# Gobang.net
KiCad netlist of a schematic drawn in Altium Designer
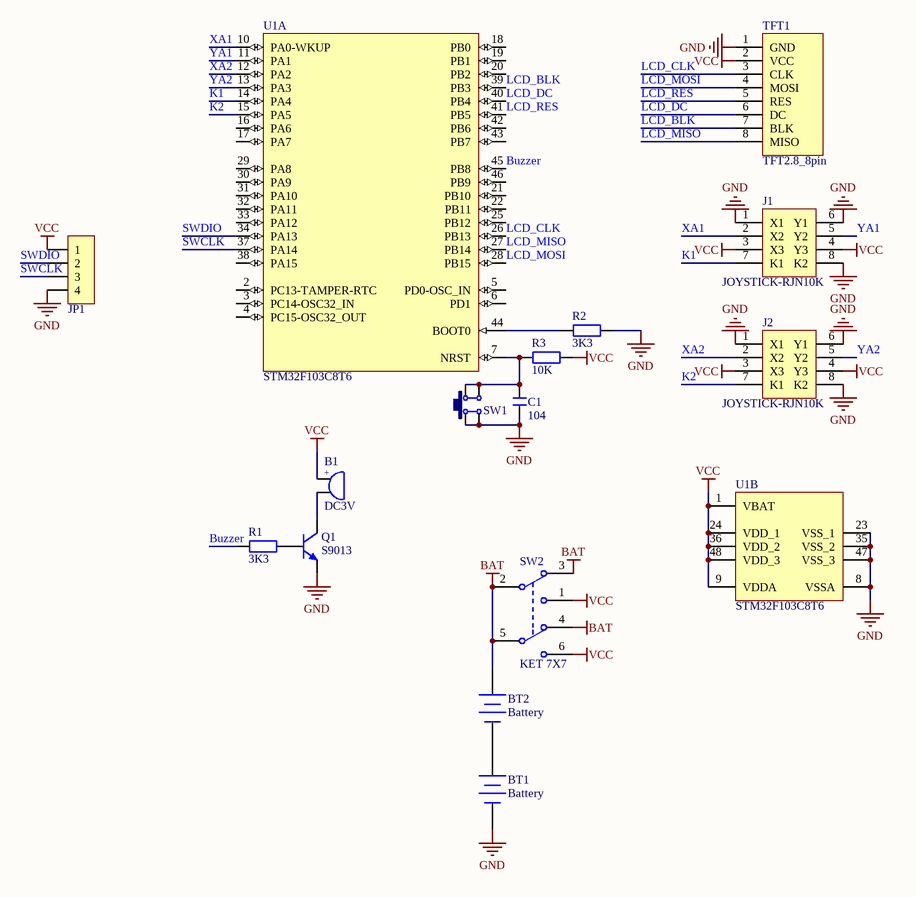
[diagram p0: Gobang.SchDoc]

(export (version "E")
  (design (tool "Eeschema 10.0.6"))
  (components
    (comp (ref "B1")
      (value "DC3V")
      (footprint "BEEP 6.5x12x8.5")
      (description "蜂鸣器")
      (fields (field (name "版权归属") "源创客"))
      (libsource (lib "未分类器件") (part "BEEP"))
    )
    (comp (ref "BT1")
      (value "Battery")
      (footprint "BATTERY AA x1")
      (description "Multicell Battery")
      (fields (field (name "PUBLISHER") "Altium Limited"))
      (libsource (lib "Miscellaneous Devices") (part "Battery"))
    )
    (comp (ref "BT2")
      (value "Battery")
      (footprint "BATTERY AA x1")
      (description "Multicell Battery")
      (fields (field (name "PUBLISHER") "Altium Limited"))
      (libsource (lib "Miscellaneous Devices") (part "Battery"))
    )
    (comp (ref "C1")
      (value "104")
      (footprint "C 0805")
      (description "无极性贴片电容")
      (fields (field (name "版权归属") "源创客"))
      (libsource (lib "电阻-电容-电感") (part "C"))
    )
    (comp (ref "J1")
      (value "JOYSTICK-RJN10K")
      (footprint "JOYSTICK-RJN10K")
      (libsource (lib "原理图库") (part "JOYSTICK-RJN10K"))
    )
    (comp (ref "J2")
      (value "JOYSTICK-RJN10K")
      (footprint "JOYSTICK-RJN10K")
      (libsource (lib "原理图库") (part "JOYSTICK-RJN10K"))
    )
    (comp (ref "JP1")
      (value "HDR-1X4")
      (footprint "HDR-1X4_H")
      (description "4P接插件")
      (fields (field (name "版权归属") "源创客"))
      (libsource (lib "接插件") (part "Header 4"))
    )
    (comp (ref "Q1")
      (value "S9013")
      (footprint "SOT23-3N")
      (description "低频放大-NPN型")
      (fields (field (name "版权归属") "源创客"))
      (libsource (lib "三极管") (part "9013-SMD"))
    )
    (comp (ref "R1")
      (value "3K3")
      (footprint "R 0603")
      (description "贴片电阻")
      (fields (field (name "版权归属") "源创客"))
      (libsource (lib "电阻-电容-电感") (part "R"))
    )
    (comp (ref "R2")
      (value "3K3")
      (footprint "R 0603")
      (description "贴片电阻")
      (fields (field (name "版权归属") "源创客"))
      (libsource (lib "电阻-电容-电感") (part "R"))
    )
    (comp (ref "R3")
      (value "10K")
      (footprint "R 0603")
      (description "贴片电阻")
      (fields (field (name "版权归属") "源创客"))
      (libsource (lib "电阻-电容-电感") (part "R"))
    )
    (comp (ref "SW1")
      (value "6x6x5")
      (footprint "TSW DIP-6*6*6")
      (description "直插6x6轻触开关")
      (fields (field (name "版权归属") "源创客"))
      (libsource (lib "按键-开关") (part "TSW DIP-6x6"))
    )
    (comp (ref "SW2")
      (value "KET 7X7")
      (footprint "KFT DIP-7X7")
      (description "7*7自锁开关")
      (fields (field (name "版权归属") "源创客"))
      (libsource (lib "按键-开关") (part "KET 7X7"))
    )
    (comp (ref "TFT1")
      (value "TFT2.8_8pin")
      (footprint "TFT2.8_8PIN")
      (description "240*320")
      (libsource (lib "显示器件") (part "TFT2.8_8pin"))
    )
    (comp (ref "U1")
      (value "STM32F103C8T6")
      (footprint "LQFP48_N")
      (libsource (lib "STMicroelectronics STM32 F1") (part "STM32F103C8T6"))
    )
  )
  (nets
    (net (code "1") (name "/Buzzer") (class "Default")
      (node (ref "R1") (pin "1") (pinfunction "1_1") (pintype "passive"))
      (node (ref "U1") (pin "45") (pinfunction "PB8_45") (pintype "bidirectional"))
    )
    (net (code "2") (name "/K1") (class "Default")
      (node (ref "J1") (pin "7") (pinfunction "K1_7") (pintype "passive"))
      (node (ref "U1") (pin "14") (pinfunction "PA4_14") (pintype "bidirectional"))
    )
    (net (code "3") (name "/K2") (class "Default")
      (node (ref "J2") (pin "7") (pinfunction "K1_7") (pintype "passive"))
      (node (ref "U1") (pin "15") (pinfunction "PA5_15") (pintype "bidirectional"))
    )
    (net (code "4") (name "/LCD_BLK") (class "Default")
      (node (ref "TFT1") (pin "7") (pinfunction "BLK_7") (pintype "passive"))
      (node (ref "U1") (pin "39") (pinfunction "PB3_39") (pintype "bidirectional"))
    )
    (net (code "5") (name "/LCD_CLK") (class "Default")
      (node (ref "TFT1") (pin "3") (pinfunction "CLK_3") (pintype "passive"))
      (node (ref "U1") (pin "26") (pinfunction "PB13_26") (pintype "bidirectional"))
    )
    (net (code "6") (name "/LCD_DC") (class "Default")
      (node (ref "TFT1") (pin "6") (pinfunction "DC_6") (pintype "passive"))
      (node (ref "U1") (pin "40") (pinfunction "PB4_40") (pintype "bidirectional"))
    )
    (net (code "7") (name "/LCD_MISO") (class "Default")
      (node (ref "TFT1") (pin "8") (pinfunction "MISO_8") (pintype "passive"))
      (node (ref "U1") (pin "27") (pinfunction "PB14_27") (pintype "bidirectional"))
    )
    (net (code "8") (name "/LCD_MOSI") (class "Default")
      (node (ref "TFT1") (pin "4") (pinfunction "MOSI_4") (pintype "passive"))
      (node (ref "U1") (pin "28") (pinfunction "PB15_28") (pintype "bidirectional"))
    )
    (net (code "9") (name "/LCD_RES") (class "Default")
      (node (ref "TFT1") (pin "5") (pinfunction "RES_5") (pintype "passive"))
      (node (ref "U1") (pin "41") (pinfunction "PB5_41") (pintype "bidirectional"))
    )
    (net (code "10") (name "/SWCLK") (class "Default")
      (node (ref "JP1") (pin "3") (pinfunction "3_3") (pintype "passive"))
      (node (ref "U1") (pin "37") (pinfunction "PA14_37") (pintype "bidirectional"))
    )
    (net (code "11") (name "/SWDIO") (class "Default")
      (node (ref "JP1") (pin "2") (pinfunction "2_2") (pintype "passive"))
      (node (ref "U1") (pin "34") (pinfunction "PA13_34") (pintype "bidirectional"))
    )
    (net (code "12") (name "/XA1") (class "Default")
      (node (ref "J1") (pin "2") (pinfunction "X2_2") (pintype "passive"))
      (node (ref "U1") (pin "10") (pinfunction "PA0-WKUP_10") (pintype "bidirectional"))
    )
    (net (code "13") (name "/XA2") (class "Default")
      (node (ref "J2") (pin "2") (pinfunction "X2_2") (pintype "passive"))
      (node (ref "U1") (pin "12") (pinfunction "PA2_12") (pintype "bidirectional"))
    )
    (net (code "14") (name "/YA1") (class "Default")
      (node (ref "J1") (pin "5") (pinfunction "Y2_5") (pintype "passive"))
      (node (ref "U1") (pin "11") (pinfunction "PA1_11") (pintype "bidirectional"))
    )
    (net (code "15") (name "/YA2") (class "Default")
      (node (ref "J2") (pin "5") (pinfunction "Y2_5") (pintype "passive"))
      (node (ref "U1") (pin "13") (pinfunction "PA3_13") (pintype "bidirectional"))
    )
    (net (code "16") (name "BAT") (class "Default")
      (node (ref "BT2") (pin "1") (pinfunction "+_1") (pintype "passive"))
      (node (ref "SW2") (pin "2") (pinfunction "COM2_2") (pintype "passive"))
      (node (ref "SW2") (pin "3") (pinfunction "NO1_3") (pintype "passive"))
      (node (ref "SW2") (pin "4") (pinfunction "NO2_4") (pintype "passive"))
      (node (ref "SW2") (pin "5") (pinfunction "COM2_5") (pintype "passive"))
    )
    (net (code "17") (name "GND") (class "Default")
      (node (ref "BT1") (pin "2") (pinfunction "-_2") (pintype "passive"))
      (node (ref "C1") (pin "1") (pinfunction "1_1") (pintype "passive"))
      (node (ref "J1") (pin "1") (pinfunction "X1_1") (pintype "passive"))
      (node (ref "J1") (pin "6") (pinfunction "Y1_6") (pintype "passive"))
      (node (ref "J1") (pin "8") (pinfunction "K2_8") (pintype "passive"))
      (node (ref "J2") (pin "1") (pinfunction "X1_1") (pintype "passive"))
      (node (ref "J2") (pin "6") (pinfunction "Y1_6") (pintype "passive"))
      (node (ref "J2") (pin "8") (pinfunction "K2_8") (pintype "passive"))
      (node (ref "JP1") (pin "4") (pinfunction "4_4") (pintype "passive"))
      (node (ref "Q1") (pin "2") (pinfunction "E_2") (pintype "passive"))
      (node (ref "R2") (pin "2") (pinfunction "2_2") (pintype "passive"))
      (node (ref "SW1") (pin "1") (pinfunction "1_1") (pintype "passive"))
      (node (ref "SW1") (pin "4") (pinfunction "4_4") (pintype "passive"))
      (node (ref "TFT1") (pin "1") (pinfunction "GND_1") (pintype "passive"))
      (node (ref "U1") (pin "23") (pinfunction "VSS_1_23") (pintype "power_in"))
      (node (ref "U1") (pin "35") (pinfunction "VSS_2_35") (pintype "power_in"))
      (node (ref "U1") (pin "47") (pinfunction "VSS_3_47") (pintype "power_in"))
      (node (ref "U1") (pin "8") (pinfunction "VSSA_8") (pintype "power_in"))
    )
    (net (code "18") (name "Net-(BT1-+)") (class "Default")
      (node (ref "BT1") (pin "1") (pinfunction "+_1") (pintype "passive"))
      (node (ref "BT2") (pin "2") (pinfunction "-_2") (pintype "passive"))
    )
    (net (code "19") (name "Net-(Q1-B)") (class "Default")
      (node (ref "Q1") (pin "1") (pinfunction "B_1") (pintype "passive"))
      (node (ref "R1") (pin "2") (pinfunction "2_2") (pintype "passive"))
    )
    (net (code "20") (name "Net-(Q1-C)") (class "Default")
      (node (ref "B1") (pin "K") (pinfunction "K_K") (pintype "passive"))
      (node (ref "Q1") (pin "3") (pinfunction "C_3") (pintype "passive"))
    )
    (net (code "21") (name "Net-(U1A-BOOT0)") (class "Default")
      (node (ref "R2") (pin "1") (pinfunction "1_1") (pintype "passive"))
      (node (ref "U1") (pin "44") (pinfunction "BOOT0_44") (pintype "input"))
    )
    (net (code "22") (name "Net-(U1A-NRST)") (class "Default")
      (node (ref "C1") (pin "2") (pinfunction "2_2") (pintype "passive"))
      (node (ref "R3") (pin "1") (pinfunction "1_1") (pintype "passive"))
      (node (ref "SW1") (pin "2") (pinfunction "2_2") (pintype "passive"))
      (node (ref "SW1") (pin "3") (pinfunction "3_3") (pintype "passive"))
      (node (ref "U1") (pin "7") (pinfunction "NRST_7") (pintype "bidirectional"))
    )
    (net (code "23") (name "VCC") (class "Default")
      (node (ref "B1") (pin "A") (pinfunction "A_A") (pintype "passive"))
      (node (ref "J1") (pin "3") (pinfunction "X3_3") (pintype "passive"))
      (node (ref "J1") (pin "4") (pinfunction "Y3_4") (pintype "passive"))
      (node (ref "J2") (pin "3") (pinfunction "X3_3") (pintype "passive"))
      (node (ref "J2") (pin "4") (pinfunction "Y3_4") (pintype "passive"))
      (node (ref "JP1") (pin "1") (pinfunction "1_1") (pintype "passive"))
      (node (ref "R3") (pin "2") (pinfunction "2_2") (pintype "passive"))
      (node (ref "SW2") (pin "1") (pinfunction "NC1_1") (pintype "passive"))
      (node (ref "SW2") (pin "6") (pinfunction "NC2_6") (pintype "passive"))
      (node (ref "TFT1") (pin "2") (pinfunction "VCC_2") (pintype "passive"))
      (node (ref "U1") (pin "1") (pinfunction "VBAT_1") (pintype "power_in"))
      (node (ref "U1") (pin "24") (pinfunction "VDD_1_24") (pintype "power_in"))
      (node (ref "U1") (pin "36") (pinfunction "VDD_2_36") (pintype "power_in"))
      (node (ref "U1") (pin "48") (pinfunction "VDD_3_48") (pintype "power_in"))
      (node (ref "U1") (pin "9") (pinfunction "VDDA_9") (pintype "power_in"))
    )
    (net (code "24") (name "unconnected-(U1A-PA6-Pad16)") (class "Default")
      (node (ref "U1") (pin "16") (pinfunction "PA6_16") (pintype "bidirectional"))
    )
    (net (code "25") (name "unconnected-(U1A-PA7-Pad17)") (class "Default")
      (node (ref "U1") (pin "17") (pinfunction "PA7_17") (pintype "bidirectional"))
    )
    (net (code "26") (name "unconnected-(U1A-PA8-Pad29)") (class "Default")
      (node (ref "U1") (pin "29") (pinfunction "PA8_29") (pintype "bidirectional"))
    )
    (net (code "27") (name "unconnected-(U1A-PA9-Pad30)") (class "Default")
      (node (ref "U1") (pin "30") (pinfunction "PA9_30") (pintype "bidirectional"))
    )
    (net (code "28") (name "unconnected-(U1A-PA10-Pad31)") (class "Default")
      (node (ref "U1") (pin "31") (pinfunction "PA10_31") (pintype "bidirectional"))
    )
    (net (code "29") (name "unconnected-(U1A-PA11-Pad32)") (class "Default")
      (node (ref "U1") (pin "32") (pinfunction "PA11_32") (pintype "bidirectional"))
    )
    (net (code "30") (name "unconnected-(U1A-PA12-Pad33)") (class "Default")
      (node (ref "U1") (pin "33") (pinfunction "PA12_33") (pintype "bidirectional"))
    )
    (net (code "31") (name "unconnected-(U1A-PA15-Pad38)") (class "Default")
      (node (ref "U1") (pin "38") (pinfunction "PA15_38") (pintype "bidirectional"))
    )
    (net (code "32") (name "unconnected-(U1A-PB0-Pad18)") (class "Default")
      (node (ref "U1") (pin "18") (pinfunction "PB0_18") (pintype "bidirectional"))
    )
    (net (code "33") (name "unconnected-(U1A-PB1-Pad19)") (class "Default")
      (node (ref "U1") (pin "19") (pinfunction "PB1_19") (pintype "bidirectional"))
    )
    (net (code "34") (name "unconnected-(U1A-PB2-Pad20)") (class "Default")
      (node (ref "U1") (pin "20") (pinfunction "PB2_20") (pintype "bidirectional"))
    )
    (net (code "35") (name "unconnected-(U1A-PB6-Pad42)") (class "Default")
      (node (ref "U1") (pin "42") (pinfunction "PB6_42") (pintype "bidirectional"))
    )
    (net (code "36") (name "unconnected-(U1A-PB7-Pad43)") (class "Default")
      (node (ref "U1") (pin "43") (pinfunction "PB7_43") (pintype "bidirectional"))
    )
    (net (code "37") (name "unconnected-(U1A-PB9-Pad46)") (class "Default")
      (node (ref "U1") (pin "46") (pinfunction "PB9_46") (pintype "bidirectional"))
    )
    (net (code "38") (name "unconnected-(U1A-PB10-Pad21)") (class "Default")
      (node (ref "U1") (pin "21") (pinfunction "PB10_21") (pintype "bidirectional"))
    )
    (net (code "39") (name "unconnected-(U1A-PB11-Pad22)") (class "Default")
      (node (ref "U1") (pin "22") (pinfunction "PB11_22") (pintype "bidirectional"))
    )
    (net (code "40") (name "unconnected-(U1A-PB12-Pad25)") (class "Default")
      (node (ref "U1") (pin "25") (pinfunction "PB12_25") (pintype "bidirectional"))
    )
    (net (code "41") (name "unconnected-(U1A-PC13-TAMPER-RTC-Pad2)") (class "Default")
      (node (ref "U1") (pin "2") (pinfunction "PC13-TAMPER-RTC_2") (pintype "bidirectional"))
    )
    (net (code "42") (name "unconnected-(U1A-PC14-OSC32_IN-Pad3)") (class "Default")
      (node (ref "U1") (pin "3") (pinfunction "PC14-OSC32_IN_3") (pintype "bidirectional"))
    )
    (net (code "43") (name "unconnected-(U1A-PC15-OSC32_OUT-Pad4)") (class "Default")
      (node (ref "U1") (pin "4") (pinfunction "PC15-OSC32_OUT_4") (pintype "bidirectional"))
    )
    (net (code "44") (name "unconnected-(U1A-PD0-OSC_IN-Pad5)") (class "Default")
      (node (ref "U1") (pin "5") (pinfunction "PD0-OSC_IN_5") (pintype "bidirectional"))
    )
    (net (code "45") (name "unconnected-(U1A-PD1-Pad6)") (class "Default")
      (node (ref "U1") (pin "6") (pinfunction "PD1_6") (pintype "bidirectional"))
    )
  )
)
